# Stereo_Audio_Codec_Breakout_WM8960.net
KiCad netlist of a schematic drawn in EAGLE
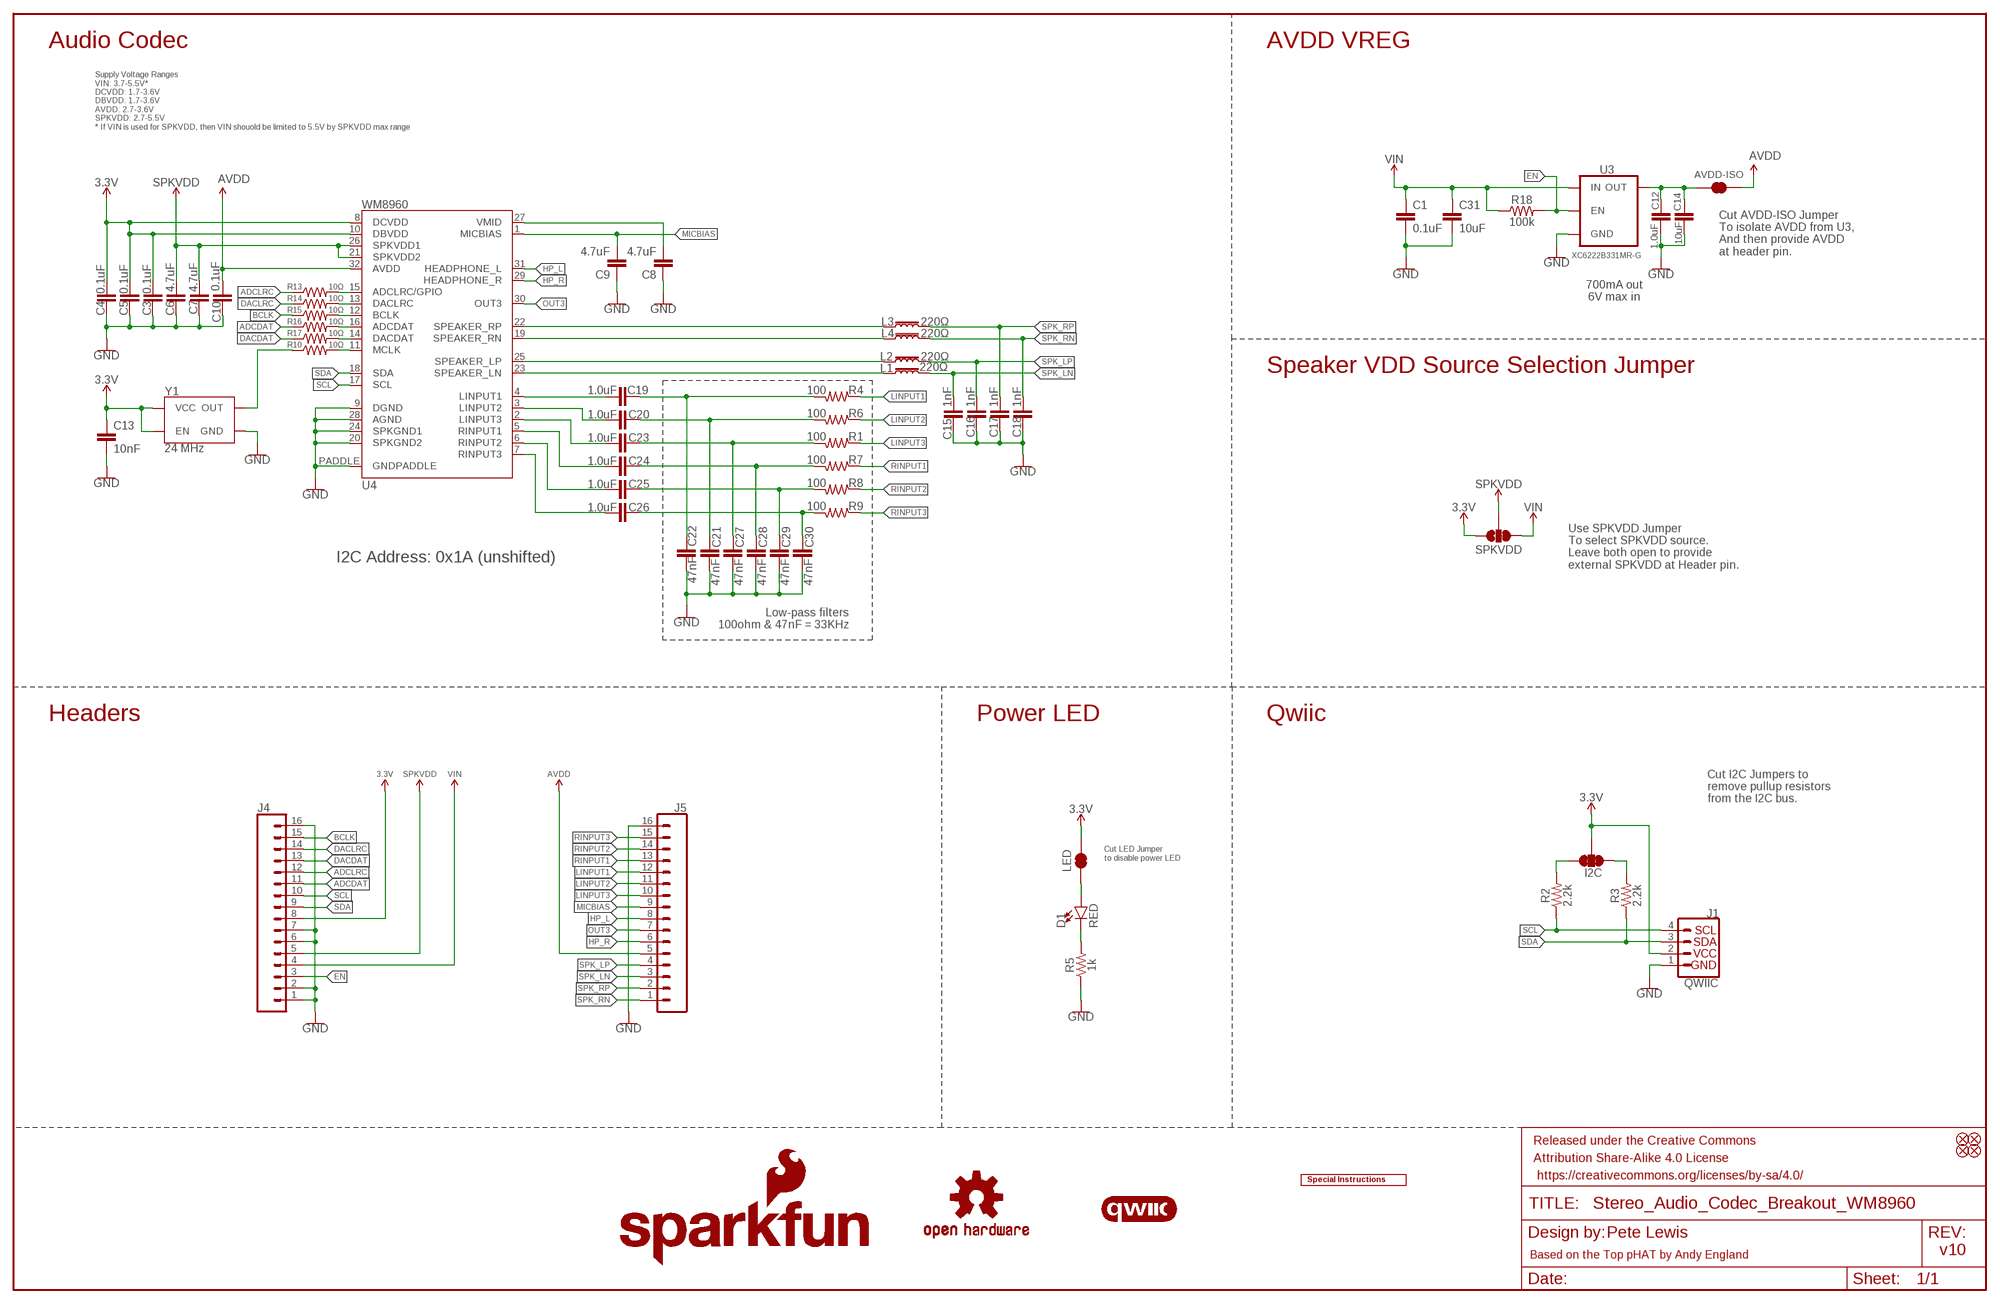
[diagram p0: schematic, sheet 1]

(export (version "E")
  (design (tool "Eeschema 10.0.6"))
  (components
    (comp (ref "AVDD-ISO")
      (value "JUMPER-SMT_2_NC_TRACE_SILK")
      (footprint "eagle-import:SMT-JUMPER_2_NC_TRACE_SILK")
      (libsource (lib "eagle-import") (part "JUMPER-SMT_2_NC_TRACE_SILK"))
    )
    (comp (ref "C1")
      (value "0.1uF")
      (footprint "eagle-import:0402-TIGHT")
      (libsource (lib "eagle-import") (part "0.1UF-0402T-16V-10%"))
    )
    (comp (ref "C3")
      (value "0.1uF")
      (footprint "eagle-import:0402-TIGHT")
      (libsource (lib "eagle-import") (part "0.1UF-0402T-16V-10%"))
    )
    (comp (ref "C4")
      (value "0.1uF")
      (footprint "eagle-import:0402-TIGHT")
      (libsource (lib "eagle-import") (part "0.1UF-0402T-16V-10%"))
    )
    (comp (ref "C5")
      (value "0.1uF")
      (footprint "eagle-import:0402-TIGHT")
      (libsource (lib "eagle-import") (part "0.1UF-0402T-16V-10%"))
    )
    (comp (ref "C6")
      (value "4.7uF")
      (footprint "eagle-import:0603")
      (libsource (lib "eagle-import") (part "4.7UF-0603-6.3V-(10%)"))
    )
    (comp (ref "C7")
      (value "4.7uF")
      (footprint "eagle-import:0603")
      (libsource (lib "eagle-import") (part "4.7UF-0603-6.3V-(10%)"))
    )
    (comp (ref "C8")
      (value "4.7uF")
      (footprint "eagle-import:0402-TIGHT")
      (libsource (lib "eagle-import") (part "4.7UF-0402_TIGHT-6.3V-20%-X5R"))
    )
    (comp (ref "C9")
      (value "4.7uF")
      (footprint "eagle-import:0402-TIGHT")
      (libsource (lib "eagle-import") (part "4.7UF-0402_TIGHT-6.3V-20%-X5R"))
    )
    (comp (ref "C10")
      (value "0.1uF")
      (footprint "eagle-import:0402-TIGHT")
      (libsource (lib "eagle-import") (part "0.1UF-0402T-16V-10%"))
    )
    (comp (ref "C12")
      (value "1.0uF")
      (footprint "eagle-import:0402-TIGHT")
      (libsource (lib "eagle-import") (part "1.0UF-0402T-16V-10%"))
    )
    (comp (ref "C13")
      (value "10nF")
      (footprint "eagle-import:0402-TIGHT")
      (libsource (lib "eagle-import") (part "10NF-0402T-25V-10%"))
    )
    (comp (ref "C14")
      (value "10uF")
      (footprint "eagle-import:0402-TIGHT")
      (libsource (lib "eagle-import") (part "10UF-0402T-6.3V-20%"))
    )
    (comp (ref "C15")
      (value "1nF")
      (footprint "eagle-import:0402")
      (libsource (lib "eagle-import") (part "1.0NF/1000PF-0402-25V-10%-X7R"))
    )
    (comp (ref "C16")
      (value "1nF")
      (footprint "eagle-import:0402")
      (libsource (lib "eagle-import") (part "1.0NF/1000PF-0402-25V-10%-X7R"))
    )
    (comp (ref "C17")
      (value "1nF")
      (footprint "eagle-import:0402")
      (libsource (lib "eagle-import") (part "1.0NF/1000PF-0402-25V-10%-X7R"))
    )
    (comp (ref "C18")
      (value "1nF")
      (footprint "eagle-import:0402")
      (libsource (lib "eagle-import") (part "1.0NF/1000PF-0402-25V-10%-X7R"))
    )
    (comp (ref "C19")
      (value "1.0uF")
      (footprint "eagle-import:0402-TIGHT")
      (libsource (lib "eagle-import") (part "1.0UF-0402T-16V-10%"))
    )
    (comp (ref "C20")
      (value "1.0uF")
      (footprint "eagle-import:0402-TIGHT")
      (libsource (lib "eagle-import") (part "1.0UF-0402T-16V-10%"))
    )
    (comp (ref "C21")
      (value "47nF")
      (footprint "eagle-import:0402-TIGHT")
      (libsource (lib "eagle-import") (part "47NF-0402_TIGHT-25V-10%-X7R"))
    )
    (comp (ref "C22")
      (value "47nF")
      (footprint "eagle-import:0402-TIGHT")
      (libsource (lib "eagle-import") (part "47NF-0402_TIGHT-25V-10%-X7R"))
    )
    (comp (ref "C23")
      (value "1.0uF")
      (footprint "eagle-import:0402-TIGHT")
      (libsource (lib "eagle-import") (part "1.0UF-0402T-16V-10%"))
    )
    (comp (ref "C24")
      (value "1.0uF")
      (footprint "eagle-import:0402-TIGHT")
      (libsource (lib "eagle-import") (part "1.0UF-0402T-16V-10%"))
    )
    (comp (ref "C25")
      (value "1.0uF")
      (footprint "eagle-import:0402-TIGHT")
      (libsource (lib "eagle-import") (part "1.0UF-0402T-16V-10%"))
    )
    (comp (ref "C26")
      (value "1.0uF")
      (footprint "eagle-import:0402-TIGHT")
      (libsource (lib "eagle-import") (part "1.0UF-0402T-16V-10%"))
    )
    (comp (ref "C27")
      (value "47nF")
      (footprint "eagle-import:0402-TIGHT")
      (libsource (lib "eagle-import") (part "47NF-0402_TIGHT-25V-10%-X7R"))
    )
    (comp (ref "C28")
      (value "47nF")
      (footprint "eagle-import:0402-TIGHT")
      (libsource (lib "eagle-import") (part "47NF-0402_TIGHT-25V-10%-X7R"))
    )
    (comp (ref "C29")
      (value "47nF")
      (footprint "eagle-import:0402-TIGHT")
      (libsource (lib "eagle-import") (part "47NF-0402_TIGHT-25V-10%-X7R"))
    )
    (comp (ref "C30")
      (value "47nF")
      (footprint "eagle-import:0402-TIGHT")
      (libsource (lib "eagle-import") (part "47NF-0402_TIGHT-25V-10%-X7R"))
    )
    (comp (ref "C31")
      (value "10uF")
      (footprint "eagle-import:0402-TIGHT")
      (libsource (lib "eagle-import") (part "10UF-0402T-6.3V-20%"))
    )
    (comp (ref "D1")
      (value "RED")
      (footprint "eagle-import:LED-0603")
      (libsource (lib "eagle-import") (part "LED-RED0603"))
    )
    (comp (ref "FD1")
      (value "FIDUCIALUFIDUCIAL")
      (footprint "eagle-import:FIDUCIAL-MICRO")
      (libsource (lib "eagle-import") (part "FIDUCIALUFIDUCIAL"))
    )
    (comp (ref "FD2")
      (value "FIDUCIALUFIDUCIAL")
      (footprint "eagle-import:FIDUCIAL-MICRO")
      (libsource (lib "eagle-import") (part "FIDUCIALUFIDUCIAL"))
    )
    (comp (ref "FD3")
      (value "FIDUCIALUFIDUCIAL")
      (footprint "eagle-import:FIDUCIAL-MICRO")
      (libsource (lib "eagle-import") (part "FIDUCIALUFIDUCIAL"))
    )
    (comp (ref "FD4")
      (value "FIDUCIALUFIDUCIAL")
      (footprint "eagle-import:FIDUCIAL-MICRO")
      (libsource (lib "eagle-import") (part "FIDUCIALUFIDUCIAL"))
    )
    (comp (ref "FRAME1")
      (value "FRAME-LEDGER")
      (footprint "eagle-import:CREATIVE_COMMONS")
      (libsource (lib "eagle-import") (part "FRAME-LEDGER"))
    )
    (comp (ref "I2C")
      (value "JUMPER-SMT_3_2-NC_TRACE_SILK")
      (footprint "eagle-import:SMT-JUMPER_3_2-NC_TRACE_SILK")
      (libsource (lib "eagle-import") (part "JUMPER-SMT_3_2-NC_TRACE_SILK"))
    )
    (comp (ref "J1")
      (value "QWIIC")
      (footprint "eagle-import:JST04_1MM_RA")
      (libsource (lib "eagle-import") (part "QWIIC_CONNECTORJS-1MM"))
    )
    (comp (ref "J4")
      (value "CONN_161X16_NO_SILK")
      (footprint "eagle-import:1X16_NO_SILK")
      (libsource (lib "eagle-import") (part "CONN_161X16_NO_SILK"))
    )
    (comp (ref "J5")
      (value "CONN_161X16_NO_SILK")
      (footprint "eagle-import:1X16_NO_SILK")
      (libsource (lib "eagle-import") (part "CONN_161X16_NO_SILK"))
    )
    (comp (ref "L1")
      (value "220Ω")
      (footprint "eagle-import:0805")
      (libsource (lib "eagle-import") (part "FERRITE_BEAD-0805-220Ω-100MHZ-2A"))
    )
    (comp (ref "L2")
      (value "220Ω")
      (footprint "eagle-import:0805")
      (libsource (lib "eagle-import") (part "FERRITE_BEAD-0805-220Ω-100MHZ-2A"))
    )
    (comp (ref "L3")
      (value "220Ω")
      (footprint "eagle-import:0805")
      (libsource (lib "eagle-import") (part "FERRITE_BEAD-0805-220Ω-100MHZ-2A"))
    )
    (comp (ref "L4")
      (value "220Ω")
      (footprint "eagle-import:0805")
      (libsource (lib "eagle-import") (part "FERRITE_BEAD-0805-220Ω-100MHZ-2A"))
    )
    (comp (ref "LED")
      (value "JUMPER-SMT_2_NC_TRACE_SILK")
      (footprint "eagle-import:SMT-JUMPER_2_NC_TRACE_SILK")
      (libsource (lib "eagle-import") (part "JUMPER-SMT_2_NC_TRACE_SILK"))
    )
    (comp (ref "LOGO1")
      (value "SFE_LOGO_NAME_FLAME.1_INCH")
      (footprint "eagle-import:SFE_LOGO_NAME_FLAME_.1")
      (libsource (lib "eagle-import") (part "SFE_LOGO_NAME_FLAME.1_INCH"))
    )
    (comp (ref "LOGO3")
      (value "QWIIC_LOGO_4MM")
      (footprint "eagle-import:QWIIC_4MM")
      (libsource (lib "eagle-import") (part "QWIIC_LOGO_4MM"))
    )
    (comp (ref "LOGO4")
      (value "OSHW-LOGOS")
      (footprint "eagle-import:OSHW-LOGO-S")
      (libsource (lib "eagle-import") (part "OSHW-LOGOS"))
    )
    (comp (ref "LOGO5")
      (value "SPECIAL_INSTRUCTIONS-ORDERING")
      (footprint "eagle-import:ORDERING_INSTRUCTIONS")
      (libsource (lib "eagle-import") (part "SPECIAL_INSTRUCTIONS-ORDERING"))
    )
    (comp (ref "R1")
      (value "100")
      (footprint "eagle-import:0402-TIGHT")
      (libsource (lib "eagle-import") (part "100OHM-0402-TIGHT-1/16W-1%"))
    )
    (comp (ref "R2")
      (value "2.2k")
      (footprint "eagle-import:0402-TIGHT")
      (libsource (lib "eagle-import") (part "2.2KOHM-0402T-1/16W-1%"))
    )
    (comp (ref "R3")
      (value "2.2k")
      (footprint "eagle-import:0402-TIGHT")
      (libsource (lib "eagle-import") (part "2.2KOHM-0402T-1/16W-1%"))
    )
    (comp (ref "R4")
      (value "100")
      (footprint "eagle-import:0402-TIGHT")
      (libsource (lib "eagle-import") (part "100OHM-0402-TIGHT-1/16W-1%"))
    )
    (comp (ref "R5")
      (value "1k")
      (footprint "eagle-import:0402-TIGHT")
      (libsource (lib "eagle-import") (part "1KOHM-0402T-1/16W-1%"))
    )
    (comp (ref "R6")
      (value "100")
      (footprint "eagle-import:0402-TIGHT")
      (libsource (lib "eagle-import") (part "100OHM-0402-TIGHT-1/16W-1%"))
    )
    (comp (ref "R7")
      (value "100")
      (footprint "eagle-import:0402-TIGHT")
      (libsource (lib "eagle-import") (part "100OHM-0402-TIGHT-1/16W-1%"))
    )
    (comp (ref "R8")
      (value "100")
      (footprint "eagle-import:0402-TIGHT")
      (libsource (lib "eagle-import") (part "100OHM-0402-TIGHT-1/16W-1%"))
    )
    (comp (ref "R9")
      (value "100")
      (footprint "eagle-import:0402-TIGHT")
      (libsource (lib "eagle-import") (part "100OHM-0402-TIGHT-1/16W-1%"))
    )
    (comp (ref "R10")
      (value "10Ω")
      (footprint "eagle-import:0402-TIGHT")
      (libsource (lib "eagle-import") (part "10OHM-0402-1/16W-5%"))
    )
    (comp (ref "R13")
      (value "10Ω")
      (footprint "eagle-import:0402-TIGHT")
      (libsource (lib "eagle-import") (part "10OHM-0402-1/16W-5%"))
    )
    (comp (ref "R14")
      (value "10Ω")
      (footprint "eagle-import:0402-TIGHT")
      (libsource (lib "eagle-import") (part "10OHM-0402-1/16W-5%"))
    )
    (comp (ref "R15")
      (value "10Ω")
      (footprint "eagle-import:0402-TIGHT")
      (libsource (lib "eagle-import") (part "10OHM-0402-1/16W-5%"))
    )
    (comp (ref "R16")
      (value "10Ω")
      (footprint "eagle-import:0402-TIGHT")
      (libsource (lib "eagle-import") (part "10OHM-0402-1/16W-5%"))
    )
    (comp (ref "R17")
      (value "10Ω")
      (footprint "eagle-import:0402-TIGHT")
      (libsource (lib "eagle-import") (part "10OHM-0402-1/16W-5%"))
    )
    (comp (ref "R18")
      (value "100k")
      (footprint "eagle-import:0402-TIGHT")
      (libsource (lib "eagle-import") (part "100KOHM-0402T-1/16W-1%"))
    )
    (comp (ref "SPKVDD")
      (value "JUMPER-SMT_3_1-NC_TRACE_SILK")
      (footprint "eagle-import:SMT-JUMPER_3_1-NC_TRACE_SILK")
      (libsource (lib "eagle-import") (part "JUMPER-SMT_3_1-NC_TRACE_SILK"))
    )
    (comp (ref "U3")
      (value "XC6222B331MR-G")
      (footprint "eagle-import:SOT23-5")
      (libsource (lib "eagle-import") (part "XC6222B331MR-G"))
    )
    (comp (ref "U4")
      (value "WM8960")
      (footprint "eagle-import:QFN-32")
      (libsource (lib "eagle-import") (part "WM8960"))
    )
    (comp (ref "Y1")
      (value "24 MHz")
      (footprint "eagle-import:RESONATOR-SMD-3.2X2.5")
      (libsource (lib "eagle-import") (part "OSCILLATOR-24MHZ"))
    )
  )
  (nets
    (net (code "1") (name "3.3V") (class "Default")
      (node (ref "C13") (pin "1") (pinfunction "1_1") (pintype "passive"))
      (node (ref "C3") (pin "2") (pinfunction "2_2") (pintype "passive"))
      (node (ref "C4") (pin "2") (pinfunction "2_2") (pintype "passive"))
      (node (ref "C5") (pin "2") (pinfunction "2_2") (pintype "passive"))
      (node (ref "I2C") (pin "2") (pinfunction "2_2") (pintype "passive"))
      (node (ref "J1") (pin "2") (pinfunction "2_2") (pintype "power_in"))
      (node (ref "J4") (pin "8") (pinfunction "8_8") (pintype "passive"))
      (node (ref "LED") (pin "2") (pinfunction "2_2") (pintype "passive"))
      (node (ref "SPKVDD") (pin "1") (pinfunction "1_1") (pintype "passive"))
      (node (ref "U4") (pin "10") (pinfunction "DBVDD_10") (pintype "bidirectional"))
      (node (ref "U4") (pin "8") (pinfunction "DCVDD_8") (pintype "bidirectional"))
      (node (ref "Y1") (pin "1") (pinfunction "EN_1") (pintype "bidirectional"))
      (node (ref "Y1") (pin "4") (pinfunction "VCC_4") (pintype "bidirectional"))
    )
    (net (code "2") (name "ADCDAT") (class "Default")
      (node (ref "J4") (pin "11") (pinfunction "11_11") (pintype "passive"))
      (node (ref "R16") (pin "1") (pinfunction "1_1") (pintype "passive"))
    )
    (net (code "3") (name "ADCLRC") (class "Default")
      (node (ref "J4") (pin "12") (pinfunction "12_12") (pintype "passive"))
      (node (ref "R13") (pin "1") (pinfunction "1_1") (pintype "passive"))
    )
    (net (code "4") (name "AVDD") (class "Default")
      (node (ref "AVDD-ISO") (pin "2") (pinfunction "2_2") (pintype "passive"))
      (node (ref "C10") (pin "2") (pinfunction "2_2") (pintype "passive"))
      (node (ref "J5") (pin "5") (pinfunction "5_5") (pintype "passive"))
      (node (ref "U4") (pin "32") (pinfunction "AVDD_32") (pintype "bidirectional"))
    )
    (net (code "5") (name "BCLK") (class "Default")
      (node (ref "J4") (pin "15") (pinfunction "15_15") (pintype "passive"))
      (node (ref "R15") (pin "1") (pinfunction "1_1") (pintype "passive"))
    )
    (net (code "6") (name "DACDAT") (class "Default")
      (node (ref "J4") (pin "13") (pinfunction "13_13") (pintype "passive"))
      (node (ref "R17") (pin "1") (pinfunction "1_1") (pintype "passive"))
    )
    (net (code "7") (name "DACLRC") (class "Default")
      (node (ref "J4") (pin "14") (pinfunction "14_14") (pintype "passive"))
      (node (ref "R14") (pin "1") (pinfunction "1_1") (pintype "passive"))
    )
    (net (code "8") (name "EN") (class "Default")
      (node (ref "J4") (pin "3") (pinfunction "3_3") (pintype "passive"))
      (node (ref "R18") (pin "2") (pinfunction "2_2") (pintype "passive"))
      (node (ref "U3") (pin "3") (pinfunction "EN_3") (pintype "input"))
    )
    (net (code "9") (name "GND") (class "Default")
      (node (ref "C1") (pin "2") (pinfunction "2_2") (pintype "passive"))
      (node (ref "C10") (pin "1") (pinfunction "1_1") (pintype "passive"))
      (node (ref "C12") (pin "2") (pinfunction "2_2") (pintype "passive"))
      (node (ref "C13") (pin "2") (pinfunction "2_2") (pintype "passive"))
      (node (ref "C14") (pin "2") (pinfunction "2_2") (pintype "passive"))
      (node (ref "C15") (pin "2") (pinfunction "2_2") (pintype "passive"))
      (node (ref "C16") (pin "2") (pinfunction "2_2") (pintype "passive"))
      (node (ref "C17") (pin "2") (pinfunction "2_2") (pintype "passive"))
      (node (ref "C18") (pin "2") (pinfunction "2_2") (pintype "passive"))
      (node (ref "C21") (pin "2") (pinfunction "2_2") (pintype "passive"))
      (node (ref "C22") (pin "2") (pinfunction "2_2") (pintype "passive"))
      (node (ref "C27") (pin "2") (pinfunction "2_2") (pintype "passive"))
      (node (ref "C28") (pin "2") (pinfunction "2_2") (pintype "passive"))
      (node (ref "C29") (pin "2") (pinfunction "2_2") (pintype "passive"))
      (node (ref "C3") (pin "1") (pinfunction "1_1") (pintype "passive"))
      (node (ref "C30") (pin "2") (pinfunction "2_2") (pintype "passive"))
      (node (ref "C31") (pin "2") (pinfunction "2_2") (pintype "passive"))
      (node (ref "C4") (pin "1") (pinfunction "1_1") (pintype "passive"))
      (node (ref "C5") (pin "1") (pinfunction "1_1") (pintype "passive"))
      (node (ref "C6") (pin "2") (pinfunction "2_2") (pintype "passive"))
      (node (ref "C7") (pin "2") (pinfunction "2_2") (pintype "passive"))
      (node (ref "C8") (pin "1") (pinfunction "1_1") (pintype "passive"))
      (node (ref "C9") (pin "1") (pinfunction "1_1") (pintype "passive"))
      (node (ref "J1") (pin "1") (pinfunction "1_1") (pintype "power_in"))
      (node (ref "J4") (pin "1") (pinfunction "1_1") (pintype "passive"))
      (node (ref "J4") (pin "16") (pinfunction "16_16") (pintype "passive"))
      (node (ref "J4") (pin "2") (pinfunction "2_2") (pintype "passive"))
      (node (ref "J4") (pin "6") (pinfunction "6_6") (pintype "passive"))
      (node (ref "J4") (pin "7") (pinfunction "7_7") (pintype "passive"))
      (node (ref "J5") (pin "16") (pinfunction "16_16") (pintype "passive"))
      (node (ref "R5") (pin "1") (pinfunction "1_1") (pintype "passive"))
      (node (ref "U3") (pin "2") (pinfunction "GND_2") (pintype "input"))
      (node (ref "U4") (pin "20") (pinfunction "SPKGND2_20") (pintype "bidirectional"))
      (node (ref "U4") (pin "24") (pinfunction "SPKGND1_24") (pintype "bidirectional"))
      (node (ref "U4") (pin "28") (pinfunction "AGND_28") (pintype "bidirectional"))
      (node (ref "U4") (pin "9") (pinfunction "DGND_9") (pintype "bidirectional"))
      (node (ref "U4") (pin "PADDLE") (pinfunction "GNDPADDLE_PADDLE") (pintype "bidirectional"))
      (node (ref "Y1") (pin "2") (pinfunction "GND_2") (pintype "bidirectional"))
    )
    (net (code "10") (name "HP_L") (class "Default")
      (node (ref "J5") (pin "8") (pinfunction "8_8") (pintype "passive"))
      (node (ref "U4") (pin "31") (pinfunction "HEADPHONE_L_31") (pintype "bidirectional"))
    )
    (net (code "11") (name "HP_R") (class "Default")
      (node (ref "J5") (pin "6") (pinfunction "6_6") (pintype "passive"))
      (node (ref "U4") (pin "29") (pinfunction "HEADPHONE_R_29") (pintype "bidirectional"))
    )
    (net (code "12") (name "LINPUT1") (class "Default")
      (node (ref "J5") (pin "12") (pinfunction "12_12") (pintype "passive"))
      (node (ref "R4") (pin "1") (pinfunction "1_1") (pintype "passive"))
    )
    (net (code "13") (name "LINPUT2") (class "Default")
      (node (ref "J5") (pin "11") (pinfunction "11_11") (pintype "passive"))
      (node (ref "R6") (pin "1") (pinfunction "1_1") (pintype "passive"))
    )
    (net (code "14") (name "LINPUT3") (class "Default")
      (node (ref "J5") (pin "10") (pinfunction "10_10") (pintype "passive"))
      (node (ref "R1") (pin "1") (pinfunction "1_1") (pintype "passive"))
    )
    (net (code "15") (name "MICBIAS") (class "Default")
      (node (ref "C9") (pin "2") (pinfunction "2_2") (pintype "passive"))
      (node (ref "J5") (pin "9") (pinfunction "9_9") (pintype "passive"))
      (node (ref "U4") (pin "1") (pinfunction "MICBIAS_1") (pintype "bidirectional"))
    )
    (net (code "16") (name "Net-(C19-Pad1)") (class "Default")
      (node (ref "C19") (pin "1") (pinfunction "1_1") (pintype "passive"))
      (node (ref "C22") (pin "1") (pinfunction "1_1") (pintype "passive"))
      (node (ref "R4") (pin "2") (pinfunction "2_2") (pintype "passive"))
    )
    (net (code "17") (name "Net-(C20-Pad1)") (class "Default")
      (node (ref "C20") (pin "1") (pinfunction "1_1") (pintype "passive"))
      (node (ref "C21") (pin "1") (pinfunction "1_1") (pintype "passive"))
      (node (ref "R6") (pin "2") (pinfunction "2_2") (pintype "passive"))
    )
    (net (code "18") (name "Net-(C23-Pad1)") (class "Default")
      (node (ref "C23") (pin "1") (pinfunction "1_1") (pintype "passive"))
      (node (ref "C27") (pin "1") (pinfunction "1_1") (pintype "passive"))
      (node (ref "R1") (pin "2") (pinfunction "2_2") (pintype "passive"))
    )
    (net (code "19") (name "Net-(C24-Pad1)") (class "Default")
      (node (ref "C24") (pin "1") (pinfunction "1_1") (pintype "passive"))
      (node (ref "C28") (pin "1") (pinfunction "1_1") (pintype "passive"))
      (node (ref "R7") (pin "2") (pinfunction "2_2") (pintype "passive"))
    )
    (net (code "20") (name "Net-(C25-Pad1)") (class "Default")
      (node (ref "C25") (pin "1") (pinfunction "1_1") (pintype "passive"))
      (node (ref "C29") (pin "1") (pinfunction "1_1") (pintype "passive"))
      (node (ref "R8") (pin "2") (pinfunction "2_2") (pintype "passive"))
    )
    (net (code "21") (name "Net-(C26-Pad1)") (class "Default")
      (node (ref "C26") (pin "1") (pinfunction "1_1") (pintype "passive"))
      (node (ref "C30") (pin "1") (pinfunction "1_1") (pintype "passive"))
      (node (ref "R9") (pin "2") (pinfunction "2_2") (pintype "passive"))
    )
    (net (code "22") (name "Net-(D1-PadA)") (class "Default")
      (node (ref "D1") (pin "A") (pinfunction "A_A") (pintype "passive"))
      (node (ref "LED") (pin "1") (pinfunction "1_1") (pintype "passive"))
    )
    (net (code "23") (name "Net-(D1-PadC)") (class "Default")
      (node (ref "D1") (pin "C") (pinfunction "C_C") (pintype "passive"))
      (node (ref "R5") (pin "2") (pinfunction "2_2") (pintype "passive"))
    )
    (net (code "24") (name "Net-(I2C-Pad1)") (class "Default")
      (node (ref "I2C") (pin "1") (pinfunction "1_1") (pintype "passive"))
      (node (ref "R3") (pin "2") (pinfunction "2_2") (pintype "passive"))
    )
    (net (code "25") (name "Net-(I2C-Pad3)") (class "Default")
      (node (ref "I2C") (pin "3") (pinfunction "3_3") (pintype "passive"))
      (node (ref "R2") (pin "2") (pinfunction "2_2") (pintype "passive"))
    )
    (net (code "26") (name "Net-(U3-OUT)") (class "Default")
      (node (ref "AVDD-ISO") (pin "1") (pinfunction "1_1") (pintype "passive"))
      (node (ref "C12") (pin "1") (pinfunction "1_1") (pintype "passive"))
      (node (ref "C14") (pin "1") (pinfunction "1_1") (pintype "passive"))
      (node (ref "U3") (pin "5") (pinfunction "OUT_5") (pintype "passive"))
    )
    (net (code "27") (name "Net-(U4-ADCDAT)") (class "Default")
      (node (ref "R16") (pin "2") (pinfunction "2_2") (pintype "passive"))
      (node (ref "U4") (pin "16") (pinfunction "ADCDAT_16") (pintype "bidirectional"))
    )
    (net (code "28") (name "Net-(U4-ADCLRC{slash}GPIO)") (class "Default")
      (node (ref "R13") (pin "2") (pinfunction "2_2") (pintype "passive"))
      (node (ref "U4") (pin "15") (pinfunction "ADCLRC/GPIO_15") (pintype "bidirectional"))
    )
    (net (code "29") (name "Net-(U4-BCLK)") (class "Default")
      (node (ref "R15") (pin "2") (pinfunction "2_2") (pintype "passive"))
      (node (ref "U4") (pin "12") (pinfunction "BCLK_12") (pintype "bidirectional"))
    )
    (net (code "30") (name "Net-(U4-DACDAT)") (class "Default")
      (node (ref "R17") (pin "2") (pinfunction "2_2") (pintype "passive"))
      (node (ref "U4") (pin "14") (pinfunction "DACDAT_14") (pintype "bidirectional"))
    )
    (net (code "31") (name "Net-(U4-DACLRC)") (class "Default")
      (node (ref "R14") (pin "2") (pinfunction "2_2") (pintype "passive"))
      (node (ref "U4") (pin "13") (pinfunction "DACLRC_13") (pintype "bidirectional"))
    )
    (net (code "32") (name "Net-(U4-LINPUT1)") (class "Default")
      (node (ref "C19") (pin "2") (pinfunction "2_2") (pintype "passive"))
      (node (ref "U4") (pin "4") (pinfunction "LINPUT1_4") (pintype "bidirectional"))
    )
    (net (code "33") (name "Net-(U4-LINPUT2)") (class "Default")
      (node (ref "C20") (pin "2") (pinfunction "2_2") (pintype "passive"))
      (node (ref "U4") (pin "3") (pinfunction "LINPUT2_3") (pintype "bidirectional"))
    )
    (net (code "34") (name "Net-(U4-LINPUT3)") (class "Default")
      (node (ref "C23") (pin "2") (pinfunction "2_2") (pintype "passive"))
      (node (ref "U4") (pin "2") (pinfunction "LINPUT3_2") (pintype "bidirectional"))
    )
    (net (code "35") (name "Net-(U4-MCLK)") (class "Default")
      (node (ref "R10") (pin "2") (pinfunction "2_2") (pintype "passive"))
      (node (ref "U4") (pin "11") (pinfunction "MCLK_11") (pintype "bidirectional"))
    )
    (net (code "36") (name "Net-(U4-RINPUT1)") (class "Default")
      (node (ref "C24") (pin "2") (pinfunction "2_2") (pintype "passive"))
      (node (ref "U4") (pin "5") (pinfunction "RINPUT1_5") (pintype "bidirectional"))
    )
    (net (code "37") (name "Net-(U4-RINPUT2)") (class "Default")
      (node (ref "C25") (pin "2") (pinfunction "2_2") (pintype "passive"))
      (node (ref "U4") (pin "6") (pinfunction "RINPUT2_6") (pintype "bidirectional"))
    )
    (net (code "38") (name "Net-(U4-RINPUT3)") (class "Default")
      (node (ref "C26") (pin "2") (pinfunction "2_2") (pintype "passive"))
      (node (ref "U4") (pin "7") (pinfunction "RINPUT3_7") (pintype "bidirectional"))
    )
    (net (code "39") (name "Net-(U4-SPEAKER_LN)") (class "Default")
      (node (ref "L1") (pin "1") (pinfunction "1_1") (pintype "passive"))
      (node (ref "U4") (pin "23") (pinfunction "SPEAKER_LN_23") (pintype "bidirectional"))
    )
    (net (code "40") (name "Net-(U4-SPEAKER_LP)") (class "Default")
      (node (ref "L2") (pin "1") (pinfunction "1_1") (pintype "passive"))
      (node (ref "U4") (pin "25") (pinfunction "SPEAKER_LP_25") (pintype "bidirectional"))
    )
    (net (code "41") (name "Net-(U4-SPEAKER_RN)") (class "Default")
      (node (ref "L4") (pin "1") (pinfunction "1_1") (pintype "passive"))
      (node (ref "U4") (pin "19") (pinfunction "SPEAKER_RN_19") (pintype "bidirectional"))
    )
    (net (code "42") (name "Net-(U4-SPEAKER_RP)") (class "Default")
      (node (ref "L3") (pin "1") (pinfunction "1_1") (pintype "passive"))
      (node (ref "U4") (pin "22") (pinfunction "SPEAKER_RP_22") (pintype "bidirectional"))
    )
    (net (code "43") (name "Net-(U4-VMID)") (class "Default")
      (node (ref "C8") (pin "2") (pinfunction "2_2") (pintype "passive"))
      (node (ref "U4") (pin "27") (pinfunction "VMID_27") (pintype "bidirectional"))
    )
    (net (code "44") (name "Net-(Y1-OUT)") (class "Default")
      (node (ref "R10") (pin "1") (pinfunction "1_1") (pintype "passive"))
      (node (ref "Y1") (pin "3") (pinfunction "OUT_3") (pintype "bidirectional"))
    )
    (net (code "45") (name "OUT3") (class "Default")
      (node (ref "J5") (pin "7") (pinfunction "7_7") (pintype "passive"))
      (node (ref "U4") (pin "30") (pinfunction "OUT3_30") (pintype "bidirectional"))
    )
    (net (code "46") (name "RINPUT1") (class "Default")
      (node (ref "J5") (pin "13") (pinfunction "13_13") (pintype "passive"))
      (node (ref "R7") (pin "1") (pinfunction "1_1") (pintype "passive"))
    )
    (net (code "47") (name "RINPUT2") (class "Default")
      (node (ref "J5") (pin "14") (pinfunction "14_14") (pintype "passive"))
      (node (ref "R8") (pin "1") (pinfunction "1_1") (pintype "passive"))
    )
    (net (code "48") (name "RINPUT3") (class "Default")
      (node (ref "J5") (pin "15") (pinfunction "15_15") (pintype "passive"))
      (node (ref "R9") (pin "1") (pinfunction "1_1") (pintype "passive"))
    )
    (net (code "49") (name "SCL") (class "Default")
      (node (ref "J1") (pin "4") (pinfunction "4_4") (pintype "passive"))
      (node (ref "J4") (pin "10") (pinfunction "10_10") (pintype "passive"))
      (node (ref "R2") (pin "1") (pinfunction "1_1") (pintype "passive"))
      (node (ref "U4") (pin "17") (pinfunction "SCL_17") (pintype "bidirectional"))
    )
    (net (code "50") (name "SDA") (class "Default")
      (node (ref "J1") (pin "3") (pinfunction "3_3") (pintype "passive"))
      (node (ref "J4") (pin "9") (pinfunction "9_9") (pintype "passive"))
      (node (ref "R3") (pin "1") (pinfunction "1_1") (pintype "passive"))
      (node (ref "U4") (pin "18") (pinfunction "SDA_18") (pintype "bidirectional"))
    )
    (net (code "51") (name "SPKVDD") (class "Default")
      (node (ref "C6") (pin "1") (pinfunction "1_1") (pintype "passive"))
      (node (ref "C7") (pin "1") (pinfunction "1_1") (pintype "passive"))
      (node (ref "J4") (pin "5") (pinfunction "5_5") (pintype "passive"))
      (node (ref "SPKVDD") (pin "2") (pinfunction "2_2") (pintype "passive"))
      (node (ref "U4") (pin "21") (pinfunction "SPKVDD2_21") (pintype "bidirectional"))
      (node (ref "U4") (pin "26") (pinfunction "SPKVDD1_26") (pintype "bidirectional"))
    )
    (net (code "52") (name "SPK_LN") (class "Default")
      (node (ref "C15") (pin "1") (pinfunction "1_1") (pintype "passive"))
      (node (ref "J5") (pin "3") (pinfunction "3_3") (pintype "passive"))
      (node (ref "L1") (pin "2") (pinfunction "2_2") (pintype "passive"))
    )
    (net (code "53") (name "SPK_LP") (class "Default")
      (node (ref "C16") (pin "1") (pinfunction "1_1") (pintype "passive"))
      (node (ref "J5") (pin "4") (pinfunction "4_4") (pintype "passive"))
      (node (ref "L2") (pin "2") (pinfunction "2_2") (pintype "passive"))
    )
    (net (code "54") (name "SPK_RN") (class "Default")
      (node (ref "C18") (pin "1") (pinfunction "1_1") (pintype "passive"))
      (node (ref "J5") (pin "1") (pinfunction "1_1") (pintype "passive"))
      (node (ref "L4") (pin "2") (pinfunction "2_2") (pintype "passive"))
    )
    (net (code "55") (name "SPK_RP") (class "Default")
      (node (ref "C17") (pin "1") (pinfunction "1_1") (pintype "passive"))
      (node (ref "J5") (pin "2") (pinfunction "2_2") (pintype "passive"))
      (node (ref "L3") (pin "2") (pinfunction "2_2") (pintype "passive"))
    )
    (net (code "56") (name "VIN") (class "Default")
      (node (ref "C1") (pin "1") (pinfunction "1_1") (pintype "passive"))
      (node (ref "C31") (pin "1") (pinfunction "1_1") (pintype "passive"))
      (node (ref "J4") (pin "4") (pinfunction "4_4") (pintype "passive"))
      (node (ref "R18") (pin "1") (pinfunction "1_1") (pintype "passive"))
      (node (ref "SPKVDD") (pin "3") (pinfunction "3_3") (pintype "passive"))
      (node (ref "U3") (pin "1") (pinfunction "IN_1") (pintype "input"))
    )
  )
)
